# LPDDR4_SDRAM-2.net
KiCad netlist of a schematic drawn in Altium Designer
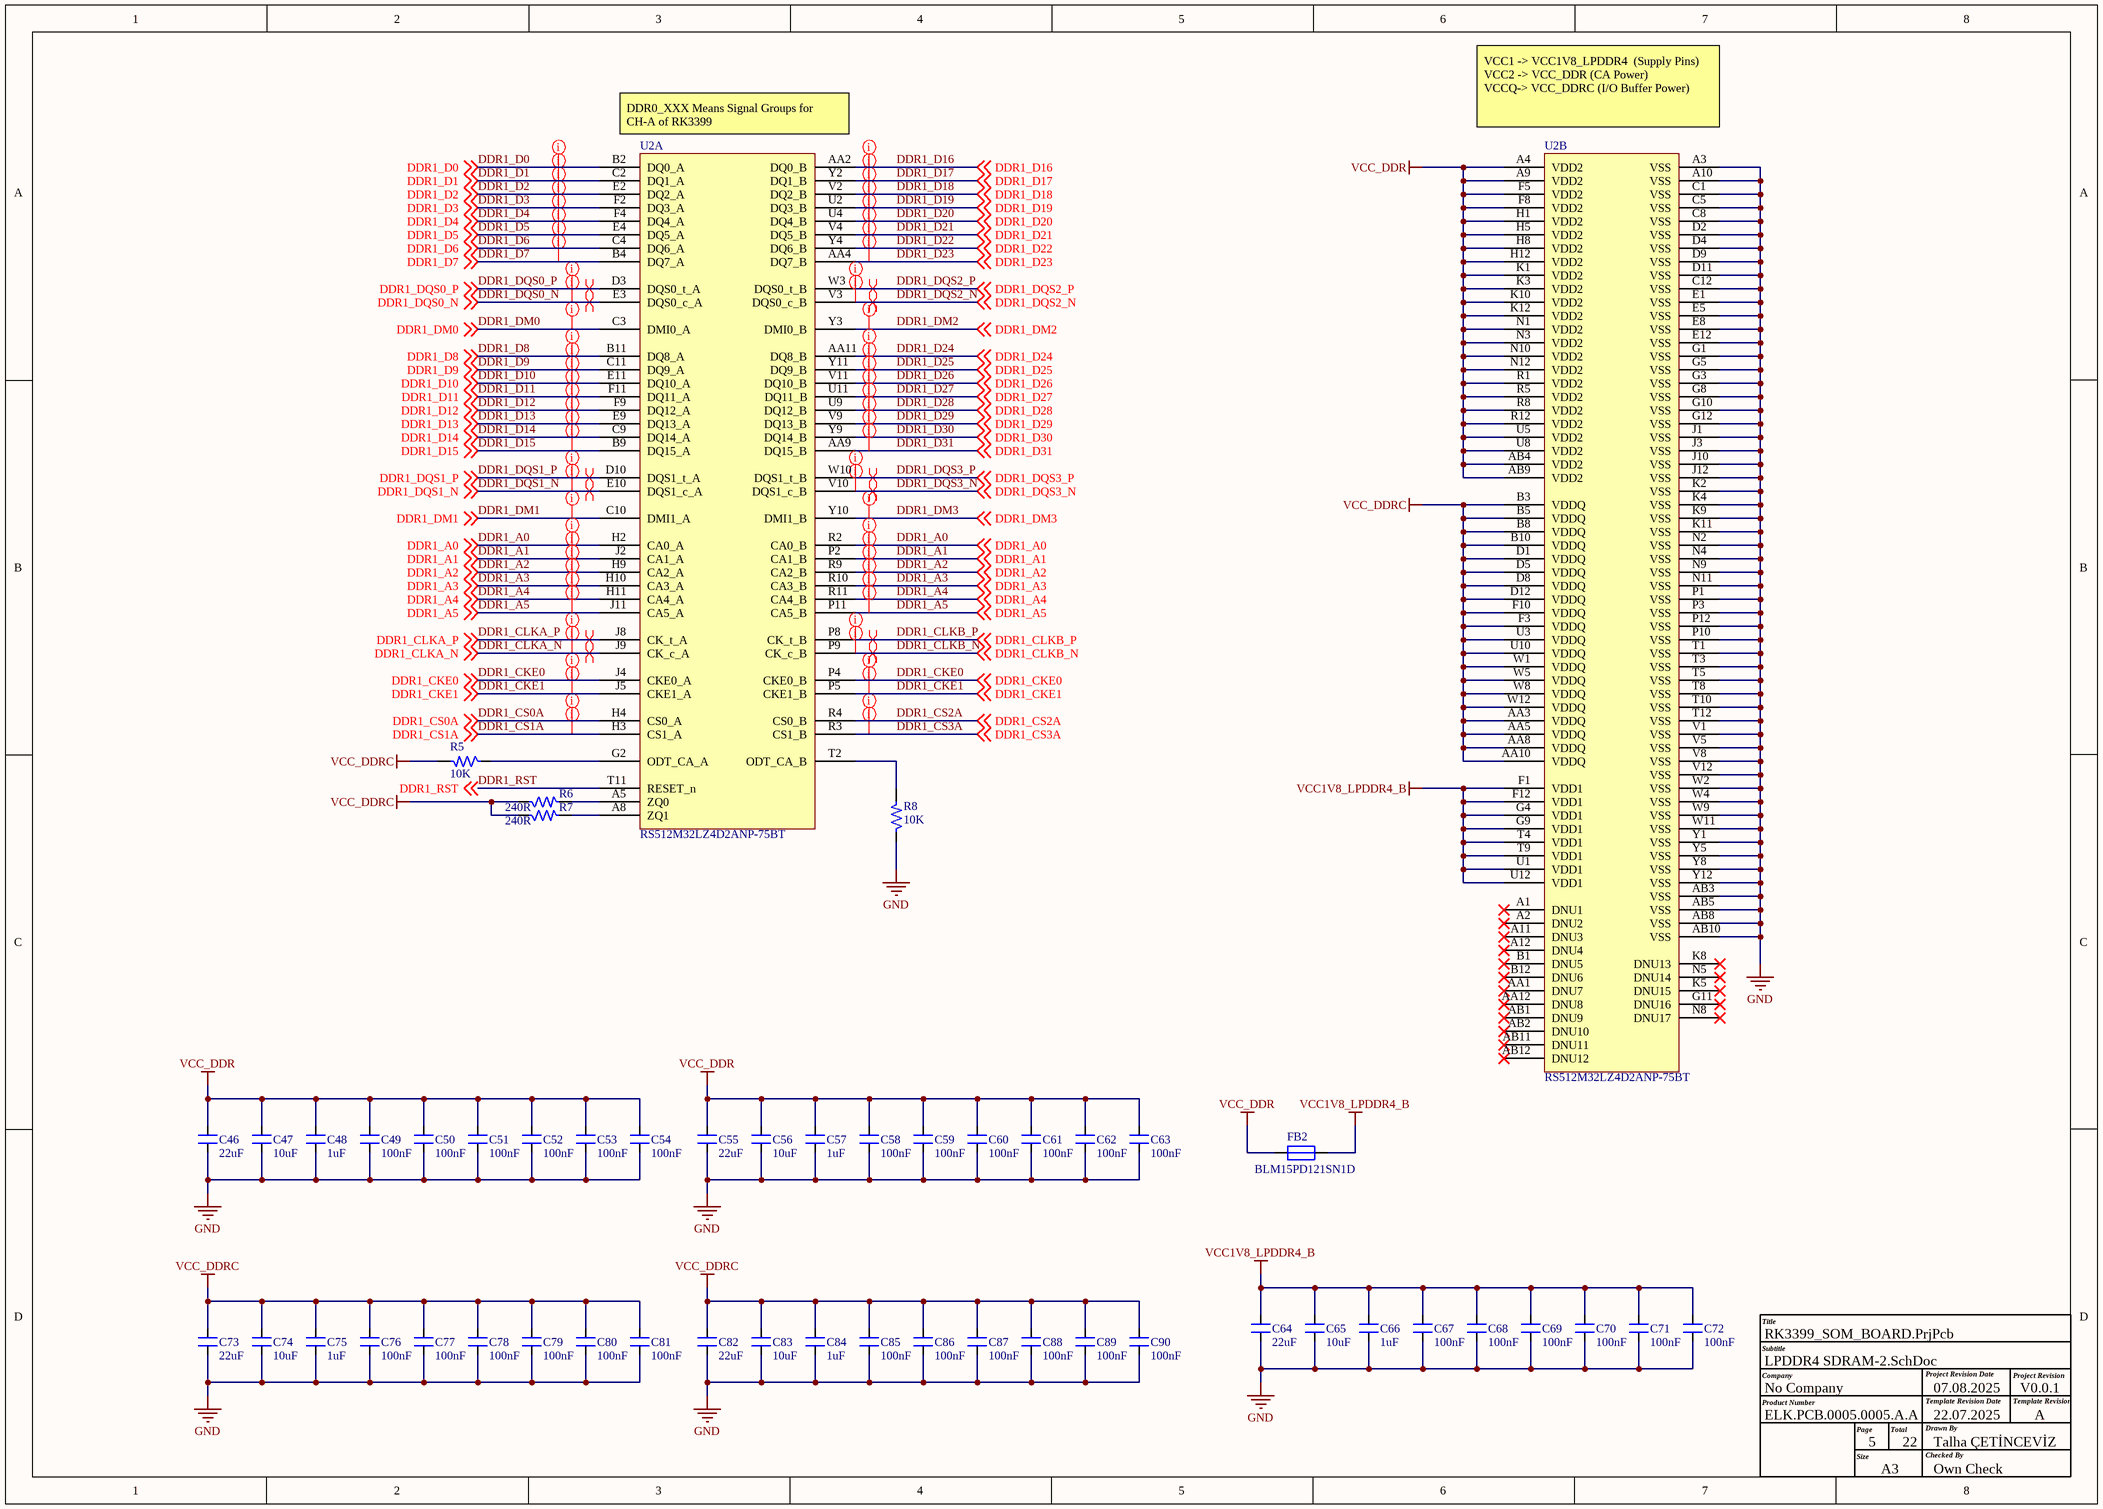
[diagram p0: LPDDR4 SDRAM-2.SchDoc]

(export (version "E")
  (design (tool "Eeschema 10.0.6"))
  (components
    (comp (ref "C46")
      (value "22uF")
      (footprint "CAP_0402")
      (description "22µF ±20% 6.3V Ceramic Capacitor X5R 0402 (1005 Metric)")
      (fields
        (field (name "MANUFACTURER") "Murata Electronics")
        (field (name "MANUFACTURER PART NUMBER") "CL05A226MQ5N6J8")
      )
      (libsource (lib "EsteemPCB_SOM_Course_intlib") (part "CAP_22uF-6.3V-20%-0402"))
    )
    (comp (ref "C47")
      (value "10uF")
      (footprint "CAP_0402")
      (description "10µF ±20% 10V Ceramic Capacitor X5R 0402 (1005 Metric)")
      (fields
        (field (name "MANUFACTURER PART NUMBER") "CL05A106MP5NUNC")
        (field (name "MANUFACTURER") "Samsung Electro-Mechanics")
      )
      (libsource (lib "EsteemPCB_SOM_Course_intlib") (part "CAP_10uF-10V-20%-0402"))
    )
    (comp (ref "C48")
      (value "1uF")
      (footprint "CAP_0201")
      (description "1µF ±20% 16V Ceramic Capacitor X5R 0201 (0603 Metric)")
      (fields
        (field (name "MANUFACTURER") "Samsung Electro-Mechanics")
        (field (name "MANUFACTURER PART NUMBER") "CL03A105MO3NRNH")
      )
      (libsource (lib "EsteemPCB_SOM_Course_intlib") (part "CAP_1uF-16V-10%-0201"))
    )
    (comp (ref "C49")
      (value "100nF")
      (footprint "CAP_0201")
      (description "0.1µF ±10% 25V Ceramic Capacitor X5R 0201 (0603 Metric)")
      (fields
        (field (name "MANUFACTURER") "TDK Corporation")
        (field (name "MANUFACTURER PART NUMBER") "C0603X5R1E104K030BB")
      )
      (libsource (lib "EsteemPCB_SOM_Course_intlib") (part "CAP_100nF-25V-10%-0201"))
    )
    (comp (ref "C50")
      (value "100nF")
      (footprint "CAP_0201")
      (description "0.1µF ±10% 25V Ceramic Capacitor X5R 0201 (0603 Metric)")
      (fields
        (field (name "MANUFACTURER") "TDK Corporation")
        (field (name "MANUFACTURER PART NUMBER") "C0603X5R1E104K030BB")
      )
      (libsource (lib "EsteemPCB_SOM_Course_intlib") (part "CAP_100nF-25V-10%-0201"))
    )
    (comp (ref "C51")
      (value "100nF")
      (footprint "CAP_0201")
      (description "0.1µF ±10% 25V Ceramic Capacitor X5R 0201 (0603 Metric)")
      (fields
        (field (name "MANUFACTURER") "TDK Corporation")
        (field (name "MANUFACTURER PART NUMBER") "C0603X5R1E104K030BB")
      )
      (libsource (lib "EsteemPCB_SOM_Course_intlib") (part "CAP_100nF-25V-10%-0201"))
    )
    (comp (ref "C52")
      (value "100nF")
      (footprint "CAP_0201")
      (description "0.1µF ±10% 25V Ceramic Capacitor X5R 0201 (0603 Metric)")
      (fields
        (field (name "MANUFACTURER") "TDK Corporation")
        (field (name "MANUFACTURER PART NUMBER") "C0603X5R1E104K030BB")
      )
      (libsource (lib "EsteemPCB_SOM_Course_intlib") (part "CAP_100nF-25V-10%-0201"))
    )
    (comp (ref "C53")
      (value "100nF")
      (footprint "CAP_0201")
      (description "0.1µF ±10% 25V Ceramic Capacitor X5R 0201 (0603 Metric)")
      (fields
        (field (name "MANUFACTURER") "TDK Corporation")
        (field (name "MANUFACTURER PART NUMBER") "C0603X5R1E104K030BB")
      )
      (libsource (lib "EsteemPCB_SOM_Course_intlib") (part "CAP_100nF-25V-10%-0201"))
    )
    (comp (ref "C54")
      (value "100nF")
      (footprint "CAP_0201")
      (description "0.1µF ±10% 25V Ceramic Capacitor X5R 0201 (0603 Metric)")
      (fields
        (field (name "MANUFACTURER") "TDK Corporation")
        (field (name "MANUFACTURER PART NUMBER") "C0603X5R1E104K030BB")
      )
      (libsource (lib "EsteemPCB_SOM_Course_intlib") (part "CAP_100nF-25V-10%-0201"))
    )
    (comp (ref "C55")
      (value "22uF")
      (footprint "CAP_0402")
      (description "22µF ±20% 6.3V Ceramic Capacitor X5R 0402 (1005 Metric)")
      (fields
        (field (name "MANUFACTURER") "Murata Electronics")
        (field (name "MANUFACTURER PART NUMBER") "CL05A226MQ5N6J8")
      )
      (libsource (lib "EsteemPCB_SOM_Course_intlib") (part "CAP_22uF-6.3V-20%-0402"))
    )
    (comp (ref "C56")
      (value "10uF")
      (footprint "CAP_0402")
      (description "10µF ±20% 10V Ceramic Capacitor X5R 0402 (1005 Metric)")
      (fields
        (field (name "MANUFACTURER PART NUMBER") "CL05A106MP5NUNC")
        (field (name "MANUFACTURER") "Samsung Electro-Mechanics")
      )
      (libsource (lib "EsteemPCB_SOM_Course_intlib") (part "CAP_10uF-10V-20%-0402"))
    )
    (comp (ref "C57")
      (value "1uF")
      (footprint "CAP_0201")
      (description "1µF ±20% 16V Ceramic Capacitor X5R 0201 (0603 Metric)")
      (fields
        (field (name "MANUFACTURER") "Samsung Electro-Mechanics")
        (field (name "MANUFACTURER PART NUMBER") "CL03A105MO3NRNH")
      )
      (libsource (lib "EsteemPCB_SOM_Course_intlib") (part "CAP_1uF-16V-10%-0201"))
    )
    (comp (ref "C58")
      (value "100nF")
      (footprint "CAP_0201")
      (description "0.1µF ±10% 25V Ceramic Capacitor X5R 0201 (0603 Metric)")
      (fields
        (field (name "MANUFACTURER") "TDK Corporation")
        (field (name "MANUFACTURER PART NUMBER") "C0603X5R1E104K030BB")
      )
      (libsource (lib "EsteemPCB_SOM_Course_intlib") (part "CAP_100nF-25V-10%-0201"))
    )
    (comp (ref "C59")
      (value "100nF")
      (footprint "CAP_0201")
      (description "0.1µF ±10% 25V Ceramic Capacitor X5R 0201 (0603 Metric)")
      (fields
        (field (name "MANUFACTURER") "TDK Corporation")
        (field (name "MANUFACTURER PART NUMBER") "C0603X5R1E104K030BB")
      )
      (libsource (lib "EsteemPCB_SOM_Course_intlib") (part "CAP_100nF-25V-10%-0201"))
    )
    (comp (ref "C60")
      (value "100nF")
      (footprint "CAP_0201")
      (description "0.1µF ±10% 25V Ceramic Capacitor X5R 0201 (0603 Metric)")
      (fields
        (field (name "MANUFACTURER") "TDK Corporation")
        (field (name "MANUFACTURER PART NUMBER") "C0603X5R1E104K030BB")
      )
      (libsource (lib "EsteemPCB_SOM_Course_intlib") (part "CAP_100nF-25V-10%-0201"))
    )
    (comp (ref "C61")
      (value "100nF")
      (footprint "CAP_0201")
      (description "0.1µF ±10% 25V Ceramic Capacitor X5R 0201 (0603 Metric)")
      (fields
        (field (name "MANUFACTURER") "TDK Corporation")
        (field (name "MANUFACTURER PART NUMBER") "C0603X5R1E104K030BB")
      )
      (libsource (lib "EsteemPCB_SOM_Course_intlib") (part "CAP_100nF-25V-10%-0201"))
    )
    (comp (ref "C62")
      (value "100nF")
      (footprint "CAP_0201")
      (description "0.1µF ±10% 25V Ceramic Capacitor X5R 0201 (0603 Metric)")
      (fields
        (field (name "MANUFACTURER") "TDK Corporation")
        (field (name "MANUFACTURER PART NUMBER") "C0603X5R1E104K030BB")
      )
      (libsource (lib "EsteemPCB_SOM_Course_intlib") (part "CAP_100nF-25V-10%-0201"))
    )
    (comp (ref "C63")
      (value "100nF")
      (footprint "CAP_0201")
      (description "0.1µF ±10% 25V Ceramic Capacitor X5R 0201 (0603 Metric)")
      (fields
        (field (name "MANUFACTURER") "TDK Corporation")
        (field (name "MANUFACTURER PART NUMBER") "C0603X5R1E104K030BB")
      )
      (libsource (lib "EsteemPCB_SOM_Course_intlib") (part "CAP_100nF-25V-10%-0201"))
    )
    (comp (ref "C64")
      (value "22uF")
      (footprint "CAP_0402")
      (description "22µF ±20% 6.3V Ceramic Capacitor X5R 0402 (1005 Metric)")
      (fields
        (field (name "MANUFACTURER") "Murata Electronics")
        (field (name "MANUFACTURER PART NUMBER") "CL05A226MQ5N6J8")
      )
      (libsource (lib "EsteemPCB_SOM_Course_intlib") (part "CAP_22uF-6.3V-20%-0402"))
    )
    (comp (ref "C65")
      (value "10uF")
      (footprint "CAP_0402")
      (description "10µF ±20% 10V Ceramic Capacitor X5R 0402 (1005 Metric)")
      (fields
        (field (name "MANUFACTURER PART NUMBER") "CL05A106MP5NUNC")
        (field (name "MANUFACTURER") "Samsung Electro-Mechanics")
      )
      (libsource (lib "EsteemPCB_SOM_Course_intlib") (part "CAP_10uF-10V-20%-0402"))
    )
    (comp (ref "C66")
      (value "1uF")
      (footprint "CAP_0201")
      (description "1µF ±20% 16V Ceramic Capacitor X5R 0201 (0603 Metric)")
      (fields
        (field (name "MANUFACTURER") "Samsung Electro-Mechanics")
        (field (name "MANUFACTURER PART NUMBER") "CL03A105MO3NRNH")
      )
      (libsource (lib "EsteemPCB_SOM_Course_intlib") (part "CAP_1uF-16V-10%-0201"))
    )
    (comp (ref "C67")
      (value "100nF")
      (footprint "CAP_0201")
      (description "0.1µF ±10% 25V Ceramic Capacitor X5R 0201 (0603 Metric)")
      (fields
        (field (name "MANUFACTURER") "TDK Corporation")
        (field (name "MANUFACTURER PART NUMBER") "C0603X5R1E104K030BB")
      )
      (libsource (lib "EsteemPCB_SOM_Course_intlib") (part "CAP_100nF-25V-10%-0201"))
    )
    (comp (ref "C68")
      (value "100nF")
      (footprint "CAP_0201")
      (description "0.1µF ±10% 25V Ceramic Capacitor X5R 0201 (0603 Metric)")
      (fields
        (field (name "MANUFACTURER") "TDK Corporation")
        (field (name "MANUFACTURER PART NUMBER") "C0603X5R1E104K030BB")
      )
      (libsource (lib "EsteemPCB_SOM_Course_intlib") (part "CAP_100nF-25V-10%-0201"))
    )
    (comp (ref "C69")
      (value "100nF")
      (footprint "CAP_0201")
      (description "0.1µF ±10% 25V Ceramic Capacitor X5R 0201 (0603 Metric)")
      (fields
        (field (name "MANUFACTURER") "TDK Corporation")
        (field (name "MANUFACTURER PART NUMBER") "C0603X5R1E104K030BB")
      )
      (libsource (lib "EsteemPCB_SOM_Course_intlib") (part "CAP_100nF-25V-10%-0201"))
    )
    (comp (ref "C70")
      (value "100nF")
      (footprint "CAP_0201")
      (description "0.1µF ±10% 25V Ceramic Capacitor X5R 0201 (0603 Metric)")
      (fields
        (field (name "MANUFACTURER") "TDK Corporation")
        (field (name "MANUFACTURER PART NUMBER") "C0603X5R1E104K030BB")
      )
      (libsource (lib "EsteemPCB_SOM_Course_intlib") (part "CAP_100nF-25V-10%-0201"))
    )
    (comp (ref "C71")
      (value "100nF")
      (footprint "CAP_0201")
      (description "0.1µF ±10% 25V Ceramic Capacitor X5R 0201 (0603 Metric)")
      (fields
        (field (name "MANUFACTURER") "TDK Corporation")
        (field (name "MANUFACTURER PART NUMBER") "C0603X5R1E104K030BB")
      )
      (libsource (lib "EsteemPCB_SOM_Course_intlib") (part "CAP_100nF-25V-10%-0201"))
    )
    (comp (ref "C72")
      (value "100nF")
      (footprint "CAP_0201")
      (description "0.1µF ±10% 25V Ceramic Capacitor X5R 0201 (0603 Metric)")
      (fields
        (field (name "MANUFACTURER") "TDK Corporation")
        (field (name "MANUFACTURER PART NUMBER") "C0603X5R1E104K030BB")
      )
      (libsource (lib "EsteemPCB_SOM_Course_intlib") (part "CAP_100nF-25V-10%-0201"))
    )
    (comp (ref "C73")
      (value "22uF")
      (footprint "CAP_0402")
      (description "22µF ±20% 6.3V Ceramic Capacitor X5R 0402 (1005 Metric)")
      (fields
        (field (name "MANUFACTURER") "Murata Electronics")
        (field (name "MANUFACTURER PART NUMBER") "CL05A226MQ5N6J8")
      )
      (libsource (lib "EsteemPCB_SOM_Course_intlib") (part "CAP_22uF-6.3V-20%-0402"))
    )
    (comp (ref "C74")
      (value "10uF")
      (footprint "CAP_0402")
      (description "10µF ±20% 10V Ceramic Capacitor X5R 0402 (1005 Metric)")
      (fields
        (field (name "MANUFACTURER PART NUMBER") "CL05A106MP5NUNC")
        (field (name "MANUFACTURER") "Samsung Electro-Mechanics")
      )
      (libsource (lib "EsteemPCB_SOM_Course_intlib") (part "CAP_10uF-10V-20%-0402"))
    )
    (comp (ref "C75")
      (value "1uF")
      (footprint "CAP_0201")
      (description "1µF ±20% 16V Ceramic Capacitor X5R 0201 (0603 Metric)")
      (fields
        (field (name "MANUFACTURER") "Samsung Electro-Mechanics")
        (field (name "MANUFACTURER PART NUMBER") "CL03A105MO3NRNH")
      )
      (libsource (lib "EsteemPCB_SOM_Course_intlib") (part "CAP_1uF-16V-10%-0201"))
    )
    (comp (ref "C76")
      (value "100nF")
      (footprint "CAP_0201")
      (description "0.1µF ±10% 25V Ceramic Capacitor X5R 0201 (0603 Metric)")
      (fields
        (field (name "MANUFACTURER") "TDK Corporation")
        (field (name "MANUFACTURER PART NUMBER") "C0603X5R1E104K030BB")
      )
      (libsource (lib "EsteemPCB_SOM_Course_intlib") (part "CAP_100nF-25V-10%-0201"))
    )
    (comp (ref "C77")
      (value "100nF")
      (footprint "CAP_0201")
      (description "0.1µF ±10% 25V Ceramic Capacitor X5R 0201 (0603 Metric)")
      (fields
        (field (name "MANUFACTURER") "TDK Corporation")
        (field (name "MANUFACTURER PART NUMBER") "C0603X5R1E104K030BB")
      )
      (libsource (lib "EsteemPCB_SOM_Course_intlib") (part "CAP_100nF-25V-10%-0201"))
    )
    (comp (ref "C78")
      (value "100nF")
      (footprint "CAP_0201")
      (description "0.1µF ±10% 25V Ceramic Capacitor X5R 0201 (0603 Metric)")
      (fields
        (field (name "MANUFACTURER") "TDK Corporation")
        (field (name "MANUFACTURER PART NUMBER") "C0603X5R1E104K030BB")
      )
      (libsource (lib "EsteemPCB_SOM_Course_intlib") (part "CAP_100nF-25V-10%-0201"))
    )
    (comp (ref "C79")
      (value "100nF")
      (footprint "CAP_0201")
      (description "0.1µF ±10% 25V Ceramic Capacitor X5R 0201 (0603 Metric)")
      (fields
        (field (name "MANUFACTURER") "TDK Corporation")
        (field (name "MANUFACTURER PART NUMBER") "C0603X5R1E104K030BB")
      )
      (libsource (lib "EsteemPCB_SOM_Course_intlib") (part "CAP_100nF-25V-10%-0201"))
    )
    (comp (ref "C80")
      (value "100nF")
      (footprint "CAP_0201")
      (description "0.1µF ±10% 25V Ceramic Capacitor X5R 0201 (0603 Metric)")
      (fields
        (field (name "MANUFACTURER") "TDK Corporation")
        (field (name "MANUFACTURER PART NUMBER") "C0603X5R1E104K030BB")
      )
      (libsource (lib "EsteemPCB_SOM_Course_intlib") (part "CAP_100nF-25V-10%-0201"))
    )
    (comp (ref "C81")
      (value "100nF")
      (footprint "CAP_0201")
      (description "0.1µF ±10% 25V Ceramic Capacitor X5R 0201 (0603 Metric)")
      (fields
        (field (name "MANUFACTURER") "TDK Corporation")
        (field (name "MANUFACTURER PART NUMBER") "C0603X5R1E104K030BB")
      )
      (libsource (lib "EsteemPCB_SOM_Course_intlib") (part "CAP_100nF-25V-10%-0201"))
    )
    (comp (ref "C82")
      (value "22uF")
      (footprint "CAP_0402")
      (description "22µF ±20% 6.3V Ceramic Capacitor X5R 0402 (1005 Metric)")
      (fields
        (field (name "MANUFACTURER") "Murata Electronics")
        (field (name "MANUFACTURER PART NUMBER") "CL05A226MQ5N6J8")
      )
      (libsource (lib "EsteemPCB_SOM_Course_intlib") (part "CAP_22uF-6.3V-20%-0402"))
    )
    (comp (ref "C83")
      (value "10uF")
      (footprint "CAP_0402")
      (description "10µF ±20% 10V Ceramic Capacitor X5R 0402 (1005 Metric)")
      (fields
        (field (name "MANUFACTURER PART NUMBER") "CL05A106MP5NUNC")
        (field (name "MANUFACTURER") "Samsung Electro-Mechanics")
      )
      (libsource (lib "EsteemPCB_SOM_Course_intlib") (part "CAP_10uF-10V-20%-0402"))
    )
    (comp (ref "C84")
      (value "1uF")
      (footprint "CAP_0201")
      (description "1µF ±20% 16V Ceramic Capacitor X5R 0201 (0603 Metric)")
      (fields
        (field (name "MANUFACTURER") "Samsung Electro-Mechanics")
        (field (name "MANUFACTURER PART NUMBER") "CL03A105MO3NRNH")
      )
      (libsource (lib "EsteemPCB_SOM_Course_intlib") (part "CAP_1uF-16V-10%-0201"))
    )
    (comp (ref "C85")
      (value "100nF")
      (footprint "CAP_0201")
      (description "0.1µF ±10% 25V Ceramic Capacitor X5R 0201 (0603 Metric)")
      (fields
        (field (name "MANUFACTURER") "TDK Corporation")
        (field (name "MANUFACTURER PART NUMBER") "C0603X5R1E104K030BB")
      )
      (libsource (lib "EsteemPCB_SOM_Course_intlib") (part "CAP_100nF-25V-10%-0201"))
    )
    (comp (ref "C86")
      (value "100nF")
      (footprint "CAP_0201")
      (description "0.1µF ±10% 25V Ceramic Capacitor X5R 0201 (0603 Metric)")
      (fields
        (field (name "MANUFACTURER") "TDK Corporation")
        (field (name "MANUFACTURER PART NUMBER") "C0603X5R1E104K030BB")
      )
      (libsource (lib "EsteemPCB_SOM_Course_intlib") (part "CAP_100nF-25V-10%-0201"))
    )
    (comp (ref "C87")
      (value "100nF")
      (footprint "CAP_0201")
      (description "0.1µF ±10% 25V Ceramic Capacitor X5R 0201 (0603 Metric)")
      (fields
        (field (name "MANUFACTURER") "TDK Corporation")
        (field (name "MANUFACTURER PART NUMBER") "C0603X5R1E104K030BB")
      )
      (libsource (lib "EsteemPCB_SOM_Course_intlib") (part "CAP_100nF-25V-10%-0201"))
    )
    (comp (ref "C88")
      (value "100nF")
      (footprint "CAP_0201")
      (description "0.1µF ±10% 25V Ceramic Capacitor X5R 0201 (0603 Metric)")
      (fields
        (field (name "MANUFACTURER") "TDK Corporation")
        (field (name "MANUFACTURER PART NUMBER") "C0603X5R1E104K030BB")
      )
      (libsource (lib "EsteemPCB_SOM_Course_intlib") (part "CAP_100nF-25V-10%-0201"))
    )
    (comp (ref "C89")
      (value "100nF")
      (footprint "CAP_0201")
      (description "0.1µF ±10% 25V Ceramic Capacitor X5R 0201 (0603 Metric)")
      (fields
        (field (name "MANUFACTURER") "TDK Corporation")
        (field (name "MANUFACTURER PART NUMBER") "C0603X5R1E104K030BB")
      )
      (libsource (lib "EsteemPCB_SOM_Course_intlib") (part "CAP_100nF-25V-10%-0201"))
    )
    (comp (ref "C90")
      (value "100nF")
      (footprint "CAP_0201")
      (description "0.1µF ±10% 25V Ceramic Capacitor X5R 0201 (0603 Metric)")
      (fields
        (field (name "MANUFACTURER") "TDK Corporation")
        (field (name "MANUFACTURER PART NUMBER") "C0603X5R1E104K030BB")
      )
      (libsource (lib "EsteemPCB_SOM_Course_intlib") (part "CAP_100nF-25V-10%-0201"))
    )
    (comp (ref "FB2")
      (value "BLM15PD121SN1D")
      (footprint "RES_0402")
      (description "120 Ohms @ 100MHz 1 Power Line Ferrite Bead 0402 (1005 Metric) 1.3A 90mOhm")
      (fields (field (name "MANUFACTURER") "Murata Electronics"))
      (libsource (lib "EsteemPCB_SOM_Course_intlib") (part "FB_120R-1.3A-100Mhz-0402"))
    )
    (comp (ref "R5")
      (value "10K")
      (footprint "RES_0201")
      (description "10 kOhms ±1% 0.05W, 1/20W Chip Resistor 0201 (0603 Metric) Thick Film")
      (fields
        (field (name "MANUFACTURER") "Stackpole Electronics Inc")
        (field (name "MANUFACTURER PART NUMBER") "RMCF0201FT10K0")
      )
      (libsource (lib "EsteemPCB_SOM_Course_intlib") (part "RES_10K-0.05W-1%-0201"))
    )
    (comp (ref "R6")
      (value "240R")
      (footprint "RES_0201")
      (description "240 Ohms ±1% 0.05W, 1/20W Chip Resistor 0201 (0603 Metric) Thick Film")
      (fields
        (field (name "MANUFACTURER") "Yageo")
        (field (name "MANUFACTURER PART NUMBER") "RC0201FR-07240RL")
      )
      (libsource (lib "EsteemPCB_SOM_Course_intlib") (part "RES_240R-0.05W-1%-0201"))
    )
    (comp (ref "R7")
      (value "240R")
      (footprint "RES_0201")
      (description "240 Ohms ±1% 0.05W, 1/20W Chip Resistor 0201 (0603 Metric) Thick Film")
      (fields
        (field (name "MANUFACTURER") "Yageo")
        (field (name "MANUFACTURER PART NUMBER") "RC0201FR-07240RL")
      )
      (libsource (lib "EsteemPCB_SOM_Course_intlib") (part "RES_240R-0.05W-1%-0201"))
    )
    (comp (ref "R8")
      (value "10K")
      (footprint "RES_0201")
      (description "10 kOhms ±1% 0.05W, 1/20W Chip Resistor 0201 (0603 Metric) Thick Film")
      (fields
        (field (name "MANUFACTURER") "Stackpole Electronics Inc")
        (field (name "MANUFACTURER PART NUMBER") "RMCF0201FT10K0")
      )
      (libsource (lib "EsteemPCB_SOM_Course_intlib") (part "RES_10K-0.05W-1%-0201"))
    )
    (comp (ref "U2")
      (value "RS512M32LZ4D2ANP-75BT")
      (footprint "FBGA200_SMD")
      (fields (field (name "MANUFACTURER") "RAYSON"))
      (libsource (lib "EsteemPCB_SOM_Course_intlib") (part "IC_RS512M32LZ4D2ANP-75BT"))
    )
  )
  (nets
    (net (code "1") (name "DDR1_A0") (class "Default")
      (node (ref "U2") (pin "H2") (pinfunction "CA0_A_H2") (pintype "passive"))
      (node (ref "U2") (pin "R2") (pinfunction "CA0_B_R2") (pintype "passive"))
    )
    (net (code "2") (name "DDR1_A1") (class "Default")
      (node (ref "U2") (pin "J2") (pinfunction "CA1_A_J2") (pintype "passive"))
      (node (ref "U2") (pin "P2") (pinfunction "CA1_B_P2") (pintype "passive"))
    )
    (net (code "3") (name "DDR1_A2") (class "Default")
      (node (ref "U2") (pin "H9") (pinfunction "CA2_A_H9") (pintype "passive"))
      (node (ref "U2") (pin "R9") (pinfunction "CA2_B_R9") (pintype "passive"))
    )
    (net (code "4") (name "DDR1_A3") (class "Default")
      (node (ref "U2") (pin "H10") (pinfunction "CA3_A_H10") (pintype "passive"))
      (node (ref "U2") (pin "R10") (pinfunction "CA3_B_R10") (pintype "passive"))
    )
    (net (code "5") (name "DDR1_A4") (class "Default")
      (node (ref "U2") (pin "H11") (pinfunction "CA4_A_H11") (pintype "passive"))
      (node (ref "U2") (pin "R11") (pinfunction "CA4_B_R11") (pintype "passive"))
    )
    (net (code "6") (name "DDR1_A5") (class "Default")
      (node (ref "U2") (pin "J11") (pinfunction "CA5_A_J11") (pintype "passive"))
      (node (ref "U2") (pin "P11") (pinfunction "CA5_B_P11") (pintype "passive"))
    )
    (net (code "7") (name "DDR1_CKE0") (class "Default")
      (node (ref "U2") (pin "J4") (pinfunction "CKE0_A_J4") (pintype "passive"))
      (node (ref "U2") (pin "P4") (pinfunction "CKE0_B_P4") (pintype "passive"))
    )
    (net (code "8") (name "DDR1_CKE1") (class "Default")
      (node (ref "U2") (pin "J5") (pinfunction "CKE1_A_J5") (pintype "passive"))
      (node (ref "U2") (pin "P5") (pinfunction "CKE1_B_P5") (pintype "passive"))
    )
    (net (code "9") (name "DDR1_CLKA_N") (class "Default")
      (node (ref "U2") (pin "J9") (pinfunction "CK_c_A_J9") (pintype "passive"))
    )
    (net (code "10") (name "DDR1_CLKA_P") (class "Default")
      (node (ref "U2") (pin "J8") (pinfunction "CK_t_A_J8") (pintype "passive"))
    )
    (net (code "11") (name "DDR1_CLKB_N") (class "Default")
      (node (ref "U2") (pin "P9") (pinfunction "CK_c_B_P9") (pintype "passive"))
    )
    (net (code "12") (name "DDR1_CLKB_P") (class "Default")
      (node (ref "U2") (pin "P8") (pinfunction "CK_t_B_P8") (pintype "passive"))
    )
    (net (code "13") (name "DDR1_CS0A") (class "Default")
      (node (ref "U2") (pin "H4") (pinfunction "CS0_A_H4") (pintype "passive"))
    )
    (net (code "14") (name "DDR1_CS1A") (class "Default")
      (node (ref "U2") (pin "H3") (pinfunction "CS1_A_H3") (pintype "passive"))
    )
    (net (code "15") (name "DDR1_CS2A") (class "Default")
      (node (ref "U2") (pin "R4") (pinfunction "CS0_B_R4") (pintype "passive"))
    )
    (net (code "16") (name "DDR1_CS3A") (class "Default")
      (node (ref "U2") (pin "R3") (pinfunction "CS1_B_R3") (pintype "passive"))
    )
    (net (code "17") (name "DDR1_D0") (class "Default")
      (node (ref "U2") (pin "B2") (pinfunction "DQ0_A_B2") (pintype "passive"))
    )
    (net (code "18") (name "DDR1_D1") (class "Default")
      (node (ref "U2") (pin "C2") (pinfunction "DQ1_A_C2") (pintype "passive"))
    )
    (net (code "19") (name "DDR1_D2") (class "Default")
      (node (ref "U2") (pin "E2") (pinfunction "DQ2_A_E2") (pintype "passive"))
    )
    (net (code "20") (name "DDR1_D3") (class "Default")
      (node (ref "U2") (pin "F2") (pinfunction "DQ3_A_F2") (pintype "passive"))
    )
    (net (code "21") (name "DDR1_D4") (class "Default")
      (node (ref "U2") (pin "F4") (pinfunction "DQ4_A_F4") (pintype "passive"))
    )
    (net (code "22") (name "DDR1_D5") (class "Default")
      (node (ref "U2") (pin "E4") (pinfunction "DQ5_A_E4") (pintype "passive"))
    )
    (net (code "23") (name "DDR1_D6") (class "Default")
      (node (ref "U2") (pin "C4") (pinfunction "DQ6_A_C4") (pintype "passive"))
    )
    (net (code "24") (name "DDR1_D7") (class "Default")
      (node (ref "U2") (pin "B4") (pinfunction "DQ7_A_B4") (pintype "passive"))
    )
    (net (code "25") (name "DDR1_D8") (class "Default")
      (node (ref "U2") (pin "B11") (pinfunction "DQ8_A_B11") (pintype "passive"))
    )
    (net (code "26") (name "DDR1_D9") (class "Default")
      (node (ref "U2") (pin "C11") (pinfunction "DQ9_A_C11") (pintype "passive"))
    )
    (net (code "27") (name "DDR1_D10") (class "Default")
      (node (ref "U2") (pin "E11") (pinfunction "DQ10_A_E11") (pintype "passive"))
    )
    (net (code "28") (name "DDR1_D11") (class "Default")
      (node (ref "U2") (pin "F11") (pinfunction "DQ11_A_F11") (pintype "passive"))
    )
    (net (code "29") (name "DDR1_D12") (class "Default")
      (node (ref "U2") (pin "F9") (pinfunction "DQ12_A_F9") (pintype "passive"))
    )
    (net (code "30") (name "DDR1_D13") (class "Default")
      (node (ref "U2") (pin "E9") (pinfunction "DQ13_A_E9") (pintype "passive"))
    )
    (net (code "31") (name "DDR1_D14") (class "Default")
      (node (ref "U2") (pin "C9") (pinfunction "DQ14_A_C9") (pintype "passive"))
    )
    (net (code "32") (name "DDR1_D15") (class "Default")
      (node (ref "U2") (pin "B9") (pinfunction "DQ15_A_B9") (pintype "passive"))
    )
    (net (code "33") (name "DDR1_D16") (class "Default")
      (node (ref "U2") (pin "AA2") (pinfunction "DQ0_B_AA2") (pintype "passive"))
    )
    (net (code "34") (name "DDR1_D17") (class "Default")
      (node (ref "U2") (pin "Y2") (pinfunction "DQ1_B_Y2") (pintype "passive"))
    )
    (net (code "35") (name "DDR1_D18") (class "Default")
      (node (ref "U2") (pin "V2") (pinfunction "DQ2_B_V2") (pintype "passive"))
    )
    (net (code "36") (name "DDR1_D19") (class "Default")
      (node (ref "U2") (pin "U2") (pinfunction "DQ3_B_U2") (pintype "passive"))
    )
    (net (code "37") (name "DDR1_D20") (class "Default")
      (node (ref "U2") (pin "U4") (pinfunction "DQ4_B_U4") (pintype "passive"))
    )
    (net (code "38") (name "DDR1_D21") (class "Default")
      (node (ref "U2") (pin "V4") (pinfunction "DQ5_B_V4") (pintype "passive"))
    )
    (net (code "39") (name "DDR1_D22") (class "Default")
      (node (ref "U2") (pin "Y4") (pinfunction "DQ6_B_Y4") (pintype "passive"))
    )
    (net (code "40") (name "DDR1_D23") (class "Default")
      (node (ref "U2") (pin "AA4") (pinfunction "DQ7_B_AA4") (pintype "passive"))
    )
    (net (code "41") (name "DDR1_D24") (class "Default")
      (node (ref "U2") (pin "AA11") (pinfunction "DQ8_B_AA11") (pintype "passive"))
    )
    (net (code "42") (name "DDR1_D25") (class "Default")
      (node (ref "U2") (pin "Y11") (pinfunction "DQ9_B_Y11") (pintype "passive"))
    )
    (net (code "43") (name "DDR1_D26") (class "Default")
      (node (ref "U2") (pin "V11") (pinfunction "DQ10_B_V11") (pintype "passive"))
    )
    (net (code "44") (name "DDR1_D27") (class "Default")
      (node (ref "U2") (pin "U11") (pinfunction "DQ11_B_U11") (pintype "passive"))
    )
    (net (code "45") (name "DDR1_D28") (class "Default")
      (node (ref "U2") (pin "U9") (pinfunction "DQ12_B_U9") (pintype "passive"))
    )
    (net (code "46") (name "DDR1_D29") (class "Default")
      (node (ref "U2") (pin "V9") (pinfunction "DQ13_B_V9") (pintype "passive"))
    )
    (net (code "47") (name "DDR1_D30") (class "Default")
      (node (ref "U2") (pin "Y9") (pinfunction "DQ14_B_Y9") (pintype "passive"))
    )
    (net (code "48") (name "DDR1_D31") (class "Default")
      (node (ref "U2") (pin "AA9") (pinfunction "DQ15_B_AA9") (pintype "passive"))
    )
    (net (code "49") (name "DDR1_DM0") (class "Default")
      (node (ref "U2") (pin "C3") (pinfunction "DMI0_A_C3") (pintype "passive"))
    )
    (net (code "50") (name "DDR1_DM1") (class "Default")
      (node (ref "U2") (pin "C10") (pinfunction "DMI1_A_C10") (pintype "passive"))
    )
    (net (code "51") (name "DDR1_DM2") (class "Default")
      (node (ref "U2") (pin "Y3") (pinfunction "DMI0_B_Y3") (pintype "passive"))
    )
    (net (code "52") (name "DDR1_DM3") (class "Default")
      (node (ref "U2") (pin "Y10") (pinfunction "DMI1_B_Y10") (pintype "passive"))
    )
    (net (code "53") (name "DDR1_DQS0_N") (class "Default")
      (node (ref "U2") (pin "E3") (pinfunction "DQS0_c_A_E3") (pintype "passive"))
    )
    (net (code "54") (name "DDR1_DQS0_P") (class "Default")
      (node (ref "U2") (pin "D3") (pinfunction "DQS0_t_A_D3") (pintype "passive"))
    )
    (net (code "55") (name "DDR1_DQS1_N") (class "Default")
      (node (ref "U2") (pin "E10") (pinfunction "DQS1_c_A_E10") (pintype "passive"))
    )
    (net (code "56") (name "DDR1_DQS1_P") (class "Default")
      (node (ref "U2") (pin "D10") (pinfunction "DQS1_t_A_D10") (pintype "passive"))
    )
    (net (code "57") (name "DDR1_DQS2_N") (class "Default")
      (node (ref "U2") (pin "V3") (pinfunction "DQS0_c_B_V3") (pintype "passive"))
    )
    (net (code "58") (name "DDR1_DQS2_P") (class "Default")
      (node (ref "U2") (pin "W3") (pinfunction "DQS0_t_B_W3") (pintype "passive"))
    )
    (net (code "59") (name "DDR1_DQS3_N") (class "Default")
      (node (ref "U2") (pin "V10") (pinfunction "DQS1_c_B_V10") (pintype "passive"))
    )
    (net (code "60") (name "DDR1_DQS3_P") (class "Default")
      (node (ref "U2") (pin "W10") (pinfunction "DQS1_t_B_W10") (pintype "passive"))
    )
    (net (code "61") (name "DDR1_RST") (class "Default")
      (node (ref "U2") (pin "T11") (pinfunction "RESET_n_T11") (pintype "passive"))
    )
    (net (code "62") (name "GND") (class "Default")
      (node (ref "C46") (pin "1") (pinfunction "1_1") (pintype "passive"))
      (node (ref "C47") (pin "1") (pinfunction "1_1") (pintype "passive"))
      (node (ref "C48") (pin "1") (pinfunction "1_1") (pintype "passive"))
      (node (ref "C49") (pin "1") (pinfunction "1_1") (pintype "passive"))
      (node (ref "C50") (pin "1") (pinfunction "1_1") (pintype "passive"))
      (node (ref "C51") (pin "1") (pinfunction "1_1") (pintype "passive"))
      (node (ref "C52") (pin "1") (pinfunction "1_1") (pintype "passive"))
      (node (ref "C53") (pin "1") (pinfunction "1_1") (pintype "passive"))
      (node (ref "C54") (pin "1") (pinfunction "1_1") (pintype "passive"))
      (node (ref "C55") (pin "1") (pinfunction "1_1") (pintype "passive"))
      (node (ref "C56") (pin "1") (pinfunction "1_1") (pintype "passive"))
      (node (ref "C57") (pin "1") (pinfunction "1_1") (pintype "passive"))
      (node (ref "C58") (pin "1") (pinfunction "1_1") (pintype "passive"))
      (node (ref "C59") (pin "1") (pinfunction "1_1") (pintype "passive"))
      (node (ref "C60") (pin "1") (pinfunction "1_1") (pintype "passive"))
      (node (ref "C61") (pin "1") (pinfunction "1_1") (pintype "passive"))
      (node (ref "C62") (pin "1") (pinfunction "1_1") (pintype "passive"))
      (node (ref "C63") (pin "1") (pinfunction "1_1") (pintype "passive"))
      (node (ref "C64") (pin "1") (pinfunction "1_1") (pintype "passive"))
      (node (ref "C65") (pin "1") (pinfunction "1_1") (pintype "passive"))
      (node (ref "C66") (pin "1") (pinfunction "1_1") (pintype "passive"))
      (node (ref "C67") (pin "1") (pinfunction "1_1") (pintype "passive"))
      (node (ref "C68") (pin "1") (pinfunction "1_1") (pintype "passive"))
      (node (ref "C69") (pin "1") (pinfunction "1_1") (pintype "passive"))
      (node (ref "C70") (pin "1") (pinfunction "1_1") (pintype "passive"))
      (node (ref "C71") (pin "1") (pinfunction "1_1") (pintype "passive"))
      (node (ref "C72") (pin "1") (pinfunction "1_1") (pintype "passive"))
      (node (ref "C73") (pin "1") (pinfunction "1_1") (pintype "passive"))
      (node (ref "C74") (pin "1") (pinfunction "1_1") (pintype "passive"))
      (node (ref "C75") (pin "1") (pinfunction "1_1") (pintype "passive"))
      (node (ref "C76") (pin "1") (pinfunction "1_1") (pintype "passive"))
      (node (ref "C77") (pin "1") (pinfunction "1_1") (pintype "passive"))
      (node (ref "C78") (pin "1") (pinfunction "1_1") (pintype "passive"))
      (node (ref "C79") (pin "1") (pinfunction "1_1") (pintype "passive"))
      (node (ref "C80") (pin "1") (pinfunction "1_1") (pintype "passive"))
      (node (ref "C81") (pin "1") (pinfunction "1_1") (pintype "passive"))
      (node (ref "C82") (pin "1") (pinfunction "1_1") (pintype "passive"))
      (node (ref "C83") (pin "1") (pinfunction "1_1") (pintype "passive"))
      (node (ref "C84") (pin "1") (pinfunction "1_1") (pintype "passive"))
      (node (ref "C85") (pin "1") (pinfunction "1_1") (pintype "passive"))
      (node (ref "C86") (pin "1") (pinfunction "1_1") (pintype "passive"))
      (node (ref "C87") (pin "1") (pinfunction "1_1") (pintype "passive"))
      (node (ref "C88") (pin "1") (pinfunction "1_1") (pintype "passive"))
      (node (ref "C89") (pin "1") (pinfunction "1_1") (pintype "passive"))
      (node (ref "C90") (pin "1") (pinfunction "1_1") (pintype "passive"))
      (node (ref "R8") (pin "1") (pinfunction "1_1") (pintype "passive"))
      (node (ref "U2") (pin "A10") (pinfunction "VSS_A10") (pintype "passive"))
      (node (ref "U2") (pin "A3") (pinfunction "VSS_A3") (pintype "passive"))
      (node (ref "U2") (pin "AB10") (pinfunction "VSS_AB10") (pintype "passive"))
      (node (ref "U2") (pin "AB3") (pinfunction "VSS_AB3") (pintype "passive"))
      (node (ref "U2") (pin "AB5") (pinfunction "VSS_AB5") (pintype "passive"))
      (node (ref "U2") (pin "AB8") (pinfunction "VSS_AB8") (pintype "passive"))
      (node (ref "U2") (pin "C1") (pinfunction "VSS_C1") (pintype "passive"))
      (node (ref "U2") (pin "C12") (pinfunction "VSS_C12") (pintype "passive"))
      (node (ref "U2") (pin "C5") (pinfunction "VSS_C5") (pintype "passive"))
      (node (ref "U2") (pin "C8") (pinfunction "VSS_C8") (pintype "passive"))
      (node (ref "U2") (pin "D11") (pinfunction "VSS_D11") (pintype "passive"))
      (node (ref "U2") (pin "D2") (pinfunction "VSS_D2") (pintype "passive"))
      (node (ref "U2") (pin "D4") (pinfunction "VSS_D4") (pintype "passive"))
      (node (ref "U2") (pin "D9") (pinfunction "VSS_D9") (pintype "passive"))
      (node (ref "U2") (pin "E1") (pinfunction "VSS_E1") (pintype "passive"))
      (node (ref "U2") (pin "E12") (pinfunction "VSS_E12") (pintype "passive"))
      (node (ref "U2") (pin "E5") (pinfunction "VSS_E5") (pintype "passive"))
      (node (ref "U2") (pin "E8") (pinfunction "VSS_E8") (pintype "passive"))
      (node (ref "U2") (pin "G1") (pinfunction "VSS_G1") (pintype "passive"))
      (node (ref "U2") (pin "G10") (pinfunction "VSS_G10") (pintype "passive"))
      (node (ref "U2") (pin "G12") (pinfunction "VSS_G12") (pintype "passive"))
      (node (ref "U2") (pin "G3") (pinfunction "VSS_G3") (pintype "passive"))
      (node (ref "U2") (pin "G5") (pinfunction "VSS_G5") (pintype "passive"))
      (node (ref "U2") (pin "G8") (pinfunction "VSS_G8") (pintype "passive"))
      (node (ref "U2") (pin "J1") (pinfunction "VSS_J1") (pintype "passive"))
      (node (ref "U2") (pin "J10") (pinfunction "VSS_J10") (pintype "passive"))
      (node (ref "U2") (pin "J12") (pinfunction "VSS_J12") (pintype "passive"))
      (node (ref "U2") (pin "J3") (pinfunction "VSS_J3") (pintype "passive"))
      (node (ref "U2") (pin "K11") (pinfunction "VSS_K11") (pintype "passive"))
      (node (ref "U2") (pin "K2") (pinfunction "VSS_K2") (pintype "passive"))
      (node (ref "U2") (pin "K4") (pinfunction "VSS_K4") (pintype "passive"))
      (node (ref "U2") (pin "K9") (pinfunction "VSS_K9") (pintype "passive"))
      (node (ref "U2") (pin "N11") (pinfunction "VSS_N11") (pintype "passive"))
      (node (ref "U2") (pin "N2") (pinfunction "VSS_N2") (pintype "passive"))
      (node (ref "U2") (pin "N4") (pinfunction "VSS_N4") (pintype "passive"))
      (node (ref "U2") (pin "N9") (pinfunction "VSS_N9") (pintype "passive"))
      (node (ref "U2") (pin "P1") (pinfunction "VSS_P1") (pintype "passive"))
      (node (ref "U2") (pin "P10") (pinfunction "VSS_P10") (pintype "passive"))
      (node (ref "U2") (pin "P12") (pinfunction "VSS_P12") (pintype "passive"))
      (node (ref "U2") (pin "P3") (pinfunction "VSS_P3") (pintype "passive"))
      (node (ref "U2") (pin "T1") (pinfunction "VSS_T1") (pintype "passive"))
      (node (ref "U2") (pin "T10") (pinfunction "VSS_T10") (pintype "passive"))
      (node (ref "U2") (pin "T12") (pinfunction "VSS_T12") (pintype "passive"))
      (node (ref "U2") (pin "T3") (pinfunction "VSS_T3") (pintype "passive"))
      (node (ref "U2") (pin "T5") (pinfunction "VSS_T5") (pintype "passive"))
      (node (ref "U2") (pin "T8") (pinfunction "VSS_T8") (pintype "passive"))
      (node (ref "U2") (pin "V1") (pinfunction "VSS_V1") (pintype "passive"))
      (node (ref "U2") (pin "V12") (pinfunction "VSS_V12") (pintype "passive"))
      (node (ref "U2") (pin "V5") (pinfunction "VSS_V5") (pintype "passive"))
      (node (ref "U2") (pin "V8") (pinfunction "VSS_V8") (pintype "passive"))
      (node (ref "U2") (pin "W11") (pinfunction "VSS_W11") (pintype "passive"))
      (node (ref "U2") (pin "W2") (pinfunction "VSS_W2") (pintype "passive"))
      (node (ref "U2") (pin "W4") (pinfunction "VSS_W4") (pintype "passive"))
      (node (ref "U2") (pin "W9") (pinfunction "VSS_W9") (pintype "passive"))
      (node (ref "U2") (pin "Y1") (pinfunction "VSS_Y1") (pintype "passive"))
      (node (ref "U2") (pin "Y12") (pinfunction "VSS_Y12") (pintype "passive"))
      (node (ref "U2") (pin "Y5") (pinfunction "VSS_Y5") (pintype "passive"))
      (node (ref "U2") (pin "Y8") (pinfunction "VSS_Y8") (pintype "passive"))
    )
    (net (code "63") (name "Net-(U2A-ODT_CA_A)") (class "Default")
      (node (ref "R5") (pin "1") (pinfunction "1_1") (pintype "passive"))
      (node (ref "U2") (pin "G2") (pinfunction "ODT_CA_A_G2") (pintype "passive"))
    )
    (net (code "64") (name "Net-(U2A-ODT_CA_B)") (class "Default")
      (node (ref "R8") (pin "2") (pinfunction "2_2") (pintype "passive"))
      (node (ref "U2") (pin "T2") (pinfunction "ODT_CA_B_T2") (pintype "passive"))
    )
    (net (code "65") (name "Net-(U2A-ZQ0)") (class "Default")
      (node (ref "R6") (pin "2") (pinfunction "2_2") (pintype "passive"))
      (node (ref "U2") (pin "A5") (pinfunction "ZQ0_A5") (pintype "passive"))
    )
    (net (code "66") (name "Net-(U2A-ZQ1)") (class "Default")
      (node (ref "R7") (pin "2") (pinfunction "2_2") (pintype "passive"))
      (node (ref "U2") (pin "A8") (pinfunction "ZQ1_A8") (pintype "passive"))
    )
    (net (code "67") (name "VCC1V8_LPDDR4_B") (class "Default")
      (node (ref "C64") (pin "2") (pinfunction "2_2") (pintype "passive"))
      (node (ref "C65") (pin "2") (pinfunction "2_2") (pintype "passive"))
      (node (ref "C66") (pin "2") (pinfunction "2_2") (pintype "passive"))
      (node (ref "C67") (pin "2") (pinfunction "2_2") (pintype "passive"))
      (node (ref "C68") (pin "2") (pinfunction "2_2") (pintype "passive"))
      (node (ref "C69") (pin "2") (pinfunction "2_2") (pintype "passive"))
      (node (ref "C70") (pin "2") (pinfunction "2_2") (pintype "passive"))
      (node (ref "C71") (pin "2") (pinfunction "2_2") (pintype "passive"))
      (node (ref "C72") (pin "2") (pinfunction "2_2") (pintype "passive"))
      (node (ref "FB2") (pin "1") (pinfunction "1_1") (pintype "passive"))
      (node (ref "U2") (pin "F1") (pinfunction "VDD1_F1") (pintype "passive"))
      (node (ref "U2") (pin "F12") (pinfunction "VDD1_F12") (pintype "passive"))
      (node (ref "U2") (pin "G4") (pinfunction "VDD1_G4") (pintype "passive"))
      (node (ref "U2") (pin "G9") (pinfunction "VDD1_G9") (pintype "passive"))
      (node (ref "U2") (pin "T4") (pinfunction "VDD1_T4") (pintype "passive"))
      (node (ref "U2") (pin "T9") (pinfunction "VDD1_T9") (pintype "passive"))
      (node (ref "U2") (pin "U1") (pinfunction "VDD1_U1") (pintype "passive"))
      (node (ref "U2") (pin "U12") (pinfunction "VDD1_U12") (pintype "passive"))
    )
    (net (code "68") (name "VCC_DDR") (class "Default")
      (node (ref "C46") (pin "2") (pinfunction "2_2") (pintype "passive"))
      (node (ref "C47") (pin "2") (pinfunction "2_2") (pintype "passive"))
      (node (ref "C48") (pin "2") (pinfunction "2_2") (pintype "passive"))
      (node (ref "C49") (pin "2") (pinfunction "2_2") (pintype "passive"))
      (node (ref "C50") (pin "2") (pinfunction "2_2") (pintype "passive"))
      (node (ref "C51") (pin "2") (pinfunction "2_2") (pintype "passive"))
      (node (ref "C52") (pin "2") (pinfunction "2_2") (pintype "passive"))
      (node (ref "C53") (pin "2") (pinfunction "2_2") (pintype "passive"))
      (node (ref "C54") (pin "2") (pinfunction "2_2") (pintype "passive"))
      (node (ref "C55") (pin "2") (pinfunction "2_2") (pintype "passive"))
      (node (ref "C56") (pin "2") (pinfunction "2_2") (pintype "passive"))
      (node (ref "C57") (pin "2") (pinfunction "2_2") (pintype "passive"))
      (node (ref "C58") (pin "2") (pinfunction "2_2") (pintype "passive"))
      (node (ref "C59") (pin "2") (pinfunction "2_2") (pintype "passive"))
      (node (ref "C60") (pin "2") (pinfunction "2_2") (pintype "passive"))
      (node (ref "C61") (pin "2") (pinfunction "2_2") (pintype "passive"))
      (node (ref "C62") (pin "2") (pinfunction "2_2") (pintype "passive"))
      (node (ref "C63") (pin "2") (pinfunction "2_2") (pintype "passive"))
      (node (ref "FB2") (pin "2") (pinfunction "2_2") (pintype "passive"))
      (node (ref "U2") (pin "A4") (pinfunction "VDD2_A4") (pintype "passive"))
      (node (ref "U2") (pin "A9") (pinfunction "VDD2_A9") (pintype "passive"))
      (node (ref "U2") (pin "AB4") (pinfunction "VDD2_AB4") (pintype "passive"))
      (node (ref "U2") (pin "AB9") (pinfunction "VDD2_AB9") (pintype "passive"))
      (node (ref "U2") (pin "F5") (pinfunction "VDD2_F5") (pintype "passive"))
      (node (ref "U2") (pin "F8") (pinfunction "VDD2_F8") (pintype "passive"))
      (node (ref "U2") (pin "H1") (pinfunction "VDD2_H1") (pintype "passive"))
      (node (ref "U2") (pin "H12") (pinfunction "VDD2_H12") (pintype "passive"))
      (node (ref "U2") (pin "H5") (pinfunction "VDD2_H5") (pintype "passive"))
      (node (ref "U2") (pin "H8") (pinfunction "VDD2_H8") (pintype "passive"))
      (node (ref "U2") (pin "K1") (pinfunction "VDD2_K1") (pintype "passive"))
      (node (ref "U2") (pin "K10") (pinfunction "VDD2_K10") (pintype "passive"))
      (node (ref "U2") (pin "K12") (pinfunction "VDD2_K12") (pintype "passive"))
      (node (ref "U2") (pin "K3") (pinfunction "VDD2_K3") (pintype "passive"))
      (node (ref "U2") (pin "N1") (pinfunction "VDD2_N1") (pintype "passive"))
      (node (ref "U2") (pin "N10") (pinfunction "VDD2_N10") (pintype "passive"))
      (node (ref "U2") (pin "N12") (pinfunction "VDD2_N12") (pintype "passive"))
      (node (ref "U2") (pin "N3") (pinfunction "VDD2_N3") (pintype "passive"))
      (node (ref "U2") (pin "R1") (pinfunction "VDD2_R1") (pintype "passive"))
      (node (ref "U2") (pin "R12") (pinfunction "VDD2_R12") (pintype "passive"))
      (node (ref "U2") (pin "R5") (pinfunction "VDD2_R5") (pintype "passive"))
      (node (ref "U2") (pin "R8") (pinfunction "VDD2_R8") (pintype "passive"))
      (node (ref "U2") (pin "U5") (pinfunction "VDD2_U5") (pintype "passive"))
      (node (ref "U2") (pin "U8") (pinfunction "VDD2_U8") (pintype "passive"))
    )
    (net (code "69") (name "VCC_DDRC") (class "Default")
      (node (ref "C73") (pin "2") (pinfunction "2_2") (pintype "passive"))
      (node (ref "C74") (pin "2") (pinfunction "2_2") (pintype "passive"))
      (node (ref "C75") (pin "2") (pinfunction "2_2") (pintype "passive"))
      (node (ref "C76") (pin "2") (pinfunction "2_2") (pintype "passive"))
      (node (ref "C77") (pin "2") (pinfunction "2_2") (pintype "passive"))
      (node (ref "C78") (pin "2") (pinfunction "2_2") (pintype "passive"))
      (node (ref "C79") (pin "2") (pinfunction "2_2") (pintype "passive"))
      (node (ref "C80") (pin "2") (pinfunction "2_2") (pintype "passive"))
      (node (ref "C81") (pin "2") (pinfunction "2_2") (pintype "passive"))
      (node (ref "C82") (pin "2") (pinfunction "2_2") (pintype "passive"))
      (node (ref "C83") (pin "2") (pinfunction "2_2") (pintype "passive"))
      (node (ref "C84") (pin "2") (pinfunction "2_2") (pintype "passive"))
      (node (ref "C85") (pin "2") (pinfunction "2_2") (pintype "passive"))
      (node (ref "C86") (pin "2") (pinfunction "2_2") (pintype "passive"))
      (node (ref "C87") (pin "2") (pinfunction "2_2") (pintype "passive"))
      (node (ref "C88") (pin "2") (pinfunction "2_2") (pintype "passive"))
      (node (ref "C89") (pin "2") (pinfunction "2_2") (pintype "passive"))
      (node (ref "C90") (pin "2") (pinfunction "2_2") (pintype "passive"))
      (node (ref "R5") (pin "2") (pinfunction "2_2") (pintype "passive"))
      (node (ref "R6") (pin "1") (pinfunction "1_1") (pintype "passive"))
      (node (ref "R7") (pin "1") (pinfunction "1_1") (pintype "passive"))
      (node (ref "U2") (pin "AA10") (pinfunction "VDDQ_AA10") (pintype "passive"))
      (node (ref "U2") (pin "AA3") (pinfunction "VDDQ_AA3") (pintype "passive"))
      (node (ref "U2") (pin "AA5") (pinfunction "VDDQ_AA5") (pintype "passive"))
      (node (ref "U2") (pin "AA8") (pinfunction "VDDQ_AA8") (pintype "passive"))
      (node (ref "U2") (pin "B10") (pinfunction "VDDQ_B10") (pintype "passive"))
      (node (ref "U2") (pin "B3") (pinfunction "VDDQ_B3") (pintype "passive"))
      (node (ref "U2") (pin "B5") (pinfunction "VDDQ_B5") (pintype "passive"))
      (node (ref "U2") (pin "B8") (pinfunction "VDDQ_B8") (pintype "passive"))
      (node (ref "U2") (pin "D1") (pinfunction "VDDQ_D1") (pintype "passive"))
      (node (ref "U2") (pin "D12") (pinfunction "VDDQ_D12") (pintype "passive"))
      (node (ref "U2") (pin "D5") (pinfunction "VDDQ_D5") (pintype "passive"))
      (node (ref "U2") (pin "D8") (pinfunction "VDDQ_D8") (pintype "passive"))
      (node (ref "U2") (pin "F10") (pinfunction "VDDQ_F10") (pintype "passive"))
      (node (ref "U2") (pin "F3") (pinfunction "VDDQ_F3") (pintype "passive"))
      (node (ref "U2") (pin "U10") (pinfunction "VDDQ_U10") (pintype "passive"))
      (node (ref "U2") (pin "U3") (pinfunction "VDDQ_U3") (pintype "passive"))
      (node (ref "U2") (pin "W1") (pinfunction "VDDQ_W1") (pintype "passive"))
      (node (ref "U2") (pin "W12") (pinfunction "VDDQ_W12") (pintype "passive"))
      (node (ref "U2") (pin "W5") (pinfunction "VDDQ_W5") (pintype "passive"))
      (node (ref "U2") (pin "W8") (pinfunction "VDDQ_W8") (pintype "passive"))
    )
    (net (code "70") (name "unconnected-(U2B-DNU1-PadA1)") (class "Default")
      (node (ref "U2") (pin "A1") (pinfunction "DNU1_A1") (pintype "passive+no_connect"))
    )
    (net (code "71") (name "unconnected-(U2B-DNU2-PadA2)") (class "Default")
      (node (ref "U2") (pin "A2") (pinfunction "DNU2_A2") (pintype "passive+no_connect"))
    )
    (net (code "72") (name "unconnected-(U2B-DNU3-PadA11)") (class "Default")
      (node (ref "U2") (pin "A11") (pinfunction "DNU3_A11") (pintype "passive+no_connect"))
    )
    (net (code "73") (name "unconnected-(U2B-DNU4-PadA12)") (class "Default")
      (node (ref "U2") (pin "A12") (pinfunction "DNU4_A12") (pintype "passive+no_connect"))
    )
    (net (code "74") (name "unconnected-(U2B-DNU5-PadB1)") (class "Default")
      (node (ref "U2") (pin "B1") (pinfunction "DNU5_B1") (pintype "passive+no_connect"))
    )
    (net (code "75") (name "unconnected-(U2B-DNU6-PadB12)") (class "Default")
      (node (ref "U2") (pin "B12") (pinfunction "DNU6_B12") (pintype "passive+no_connect"))
    )
    (net (code "76") (name "unconnected-(U2B-DNU7-PadAA1)") (class "Default")
      (node (ref "U2") (pin "AA1") (pinfunction "DNU7_AA1") (pintype "passive+no_connect"))
    )
    (net (code "77") (name "unconnected-(U2B-DNU8-PadAA12)") (class "Default")
      (node (ref "U2") (pin "AA12") (pinfunction "DNU8_AA12") (pintype "passive+no_connect"))
    )
    (net (code "78") (name "unconnected-(U2B-DNU9-PadAB1)") (class "Default")
      (node (ref "U2") (pin "AB1") (pinfunction "DNU9_AB1") (pintype "passive+no_connect"))
    )
    (net (code "79") (name "unconnected-(U2B-DNU10-PadAB2)") (class "Default")
      (node (ref "U2") (pin "AB2") (pinfunction "DNU10_AB2") (pintype "passive+no_connect"))
    )
    (net (code "80") (name "unconnected-(U2B-DNU11-PadAB11)") (class "Default")
      (node (ref "U2") (pin "AB11") (pinfunction "DNU11_AB11") (pintype "passive+no_connect"))
    )
    (net (code "81") (name "unconnected-(U2B-DNU12-PadAB12)") (class "Default")
      (node (ref "U2") (pin "AB12") (pinfunction "DNU12_AB12") (pintype "passive+no_connect"))
    )
    (net (code "82") (name "unconnected-(U2B-DNU13-PadK8)") (class "Default")
      (node (ref "U2") (pin "K8") (pinfunction "DNU13_K8") (pintype "passive+no_connect"))
    )
    (net (code "83") (name "unconnected-(U2B-DNU14-PadN5)") (class "Default")
      (node (ref "U2") (pin "N5") (pinfunction "DNU14_N5") (pintype "passive+no_connect"))
    )
    (net (code "84") (name "unconnected-(U2B-DNU15-PadK5)") (class "Default")
      (node (ref "U2") (pin "K5") (pinfunction "DNU15_K5") (pintype "passive+no_connect"))
    )
    (net (code "85") (name "unconnected-(U2B-DNU16-PadG11)") (class "Default")
      (node (ref "U2") (pin "G11") (pinfunction "DNU16_G11") (pintype "passive+no_connect"))
    )
    (net (code "86") (name "unconnected-(U2B-DNU17-PadN8)") (class "Default")
      (node (ref "U2") (pin "N8") (pinfunction "DNU17_N8") (pintype "passive+no_connect"))
    )
  )
)
